# Analog_Signal_Filter.net
KiCad netlist of a schematic drawn in Altium Designer
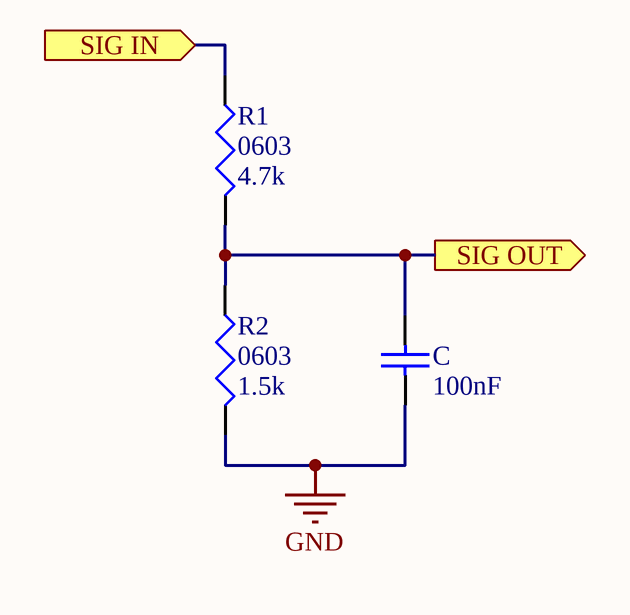
[diagram p0: Analog Signal Filter.SchDoc]

(export (version "E")
  (design (tool "Eeschema 10.0.6"))
  (components
    (comp (ref "C")
      (value "100nF")
      (footprint "CAPC1608X95X40ML15T15")
      (fields (field (name "MANUFACTURER") "Vitramon") (field (name "PART NUMBER") "VJ0603Y104KXQCW1BC"))
      (libsource (lib "Altium Content Vault") (part "CAP"))
    )
    (comp (ref "R1")
      (value "0603")
      (footprint "J1-0603")
      (description "Resistor")
      (fields (field (name "ALTIUM_VALUE") "4.7k") (field (name "PUBLISHER") "Altium Limited"))
      (libsource (lib "Miscellaneous Devices") (part "Res3"))
    )
    (comp (ref "R2")
      (value "0603")
      (footprint "J1-0603")
      (description "Resistor")
      (fields (field (name "ALTIUM_VALUE") "1.5k") (field (name "PUBLISHER") "Altium Limited"))
      (libsource (lib "Miscellaneous Devices") (part "Res3"))
    )
  )
  (nets
    (net (code "1") (name "/SIG IN") (class "Default")
      (node (ref "R1") (pin "1") (pinfunction "1_1") (pintype "passive"))
    )
    (net (code "2") (name "/SIG OUT") (class "Default")
      (node (ref "C") (pin "2") (pinfunction "2_2") (pintype "passive"))
      (node (ref "R1") (pin "2") (pinfunction "2_2") (pintype "passive"))
      (node (ref "R2") (pin "1") (pinfunction "1_1") (pintype "passive"))
    )
    (net (code "3") (name "GND") (class "Default")
      (node (ref "C") (pin "1") (pinfunction "1_1") (pintype "passive"))
      (node (ref "R2") (pin "2") (pinfunction "2_2") (pintype "passive"))
    )
  )
)
